# ProPrj_SW4_poor.net
KiCad netlist of a schematic drawn in EasyEDA Pro
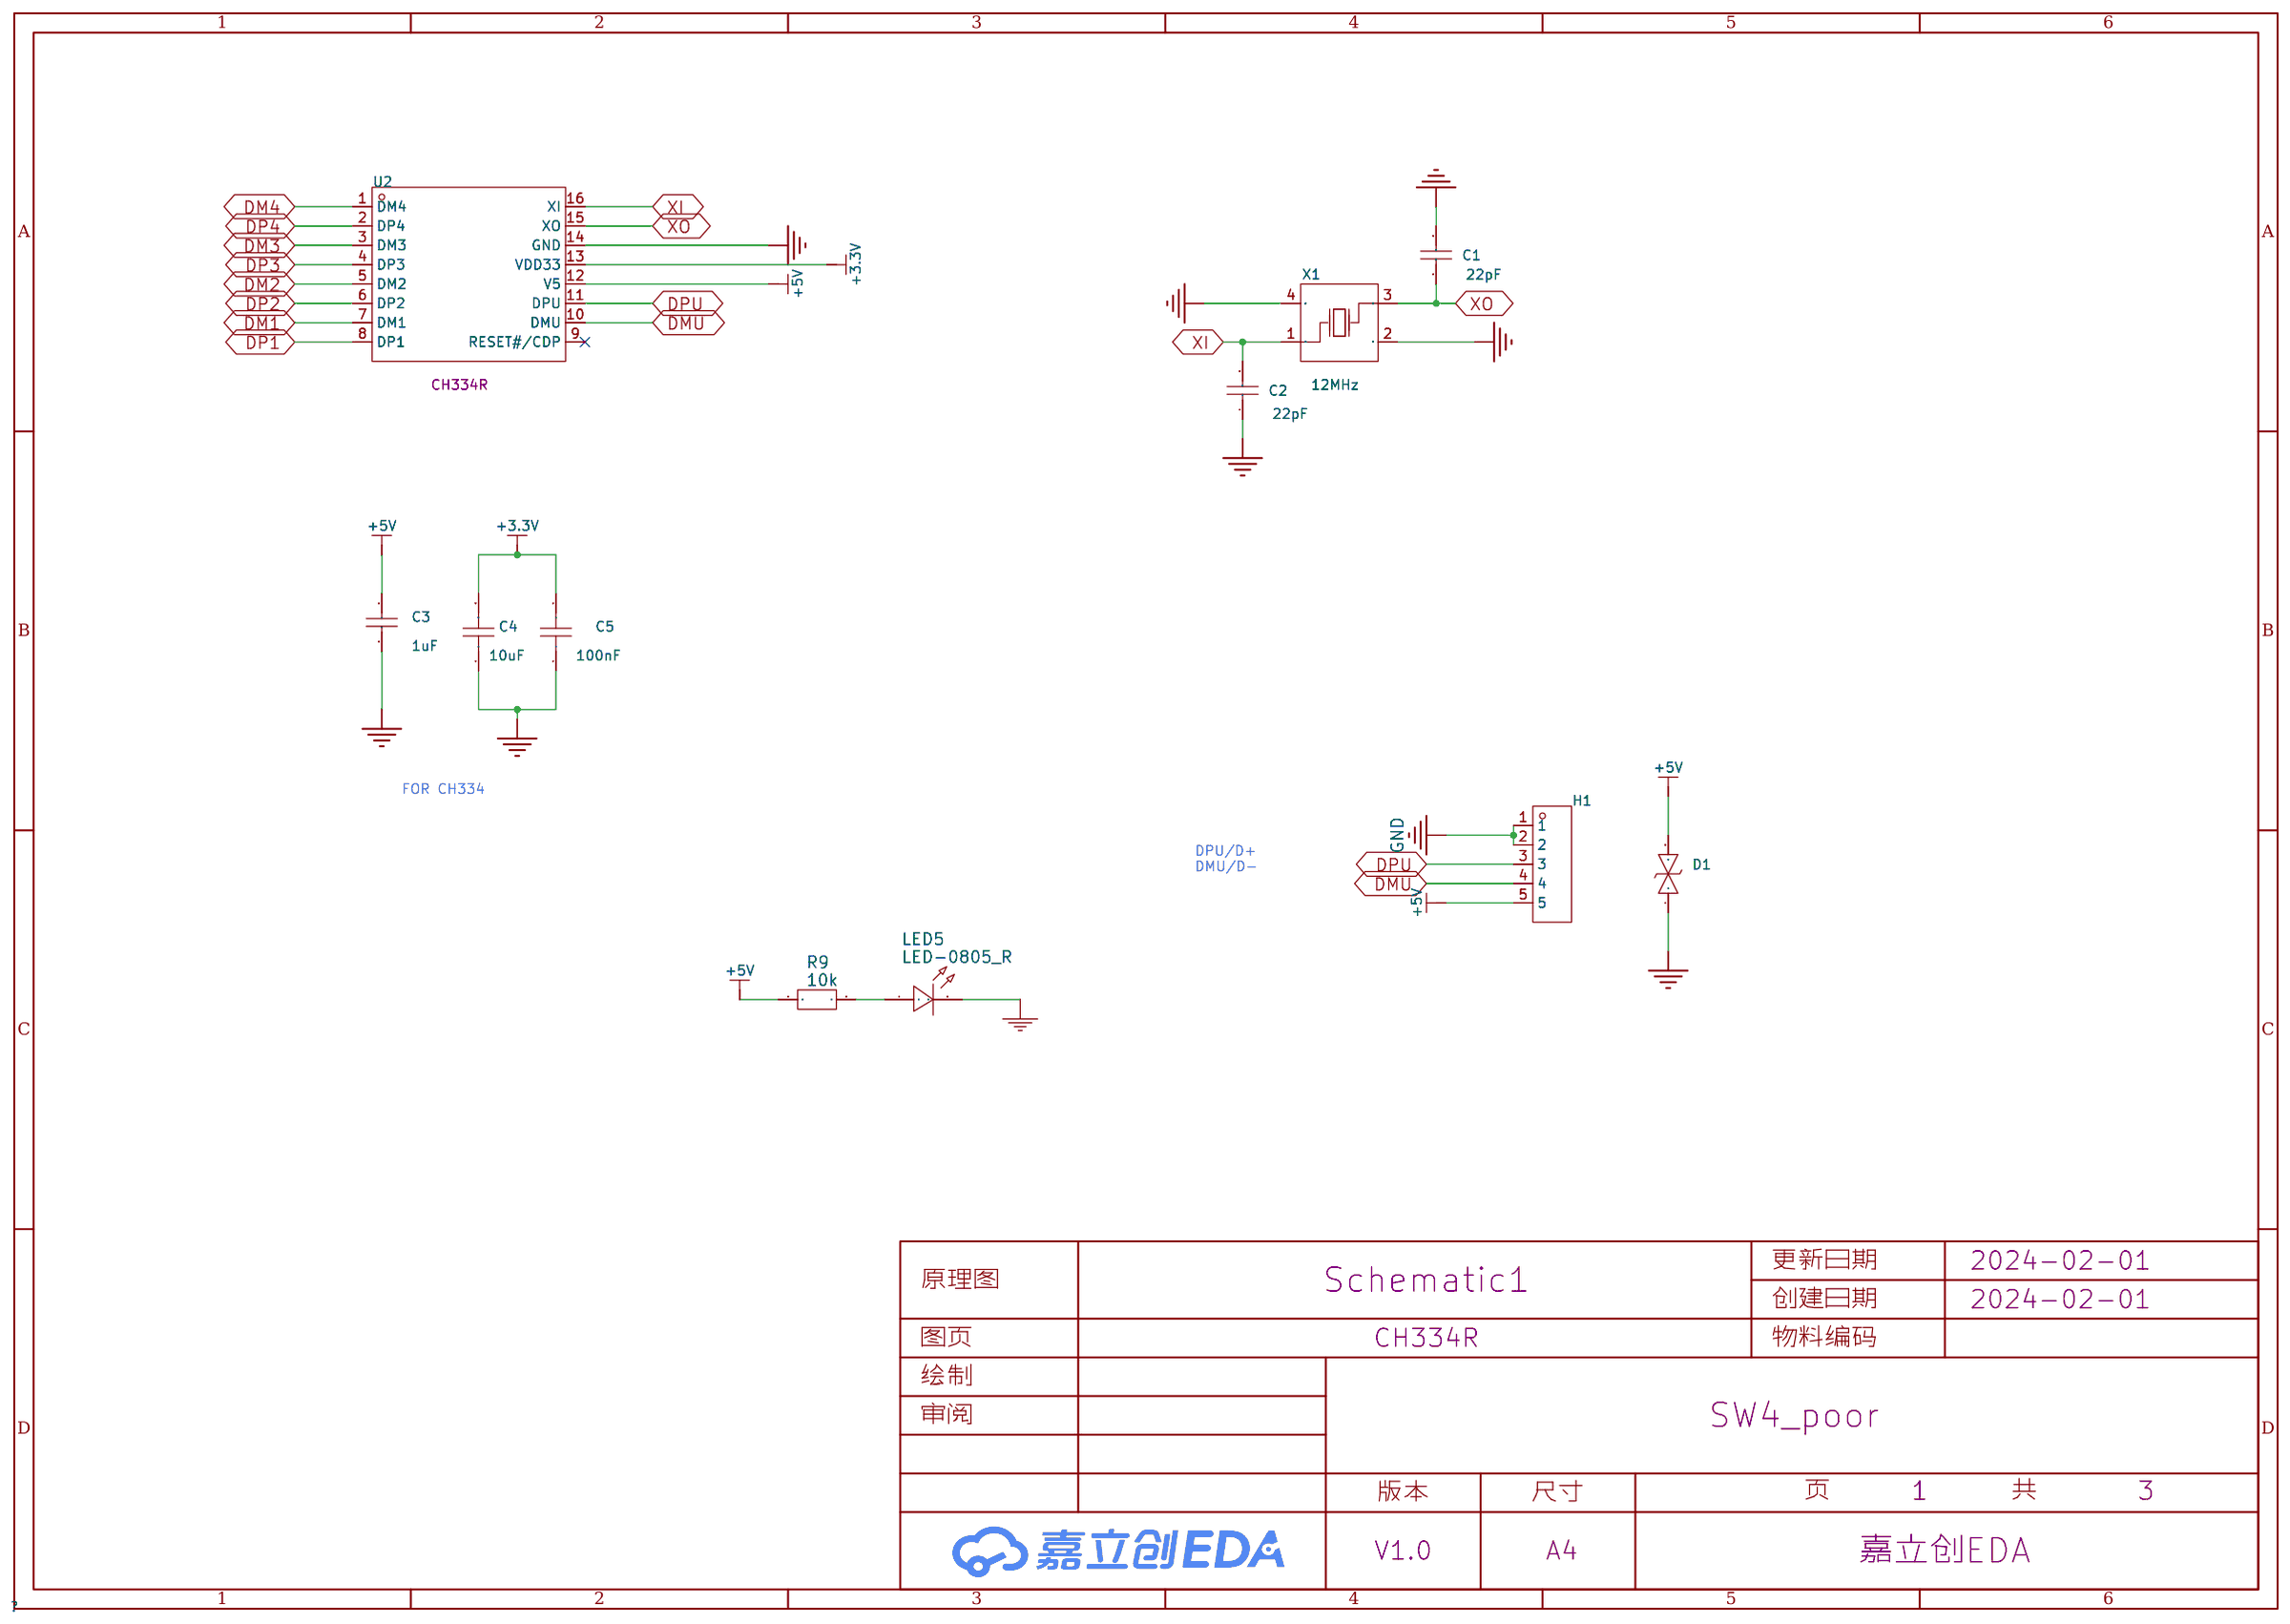
[diagram p0: CH334R]
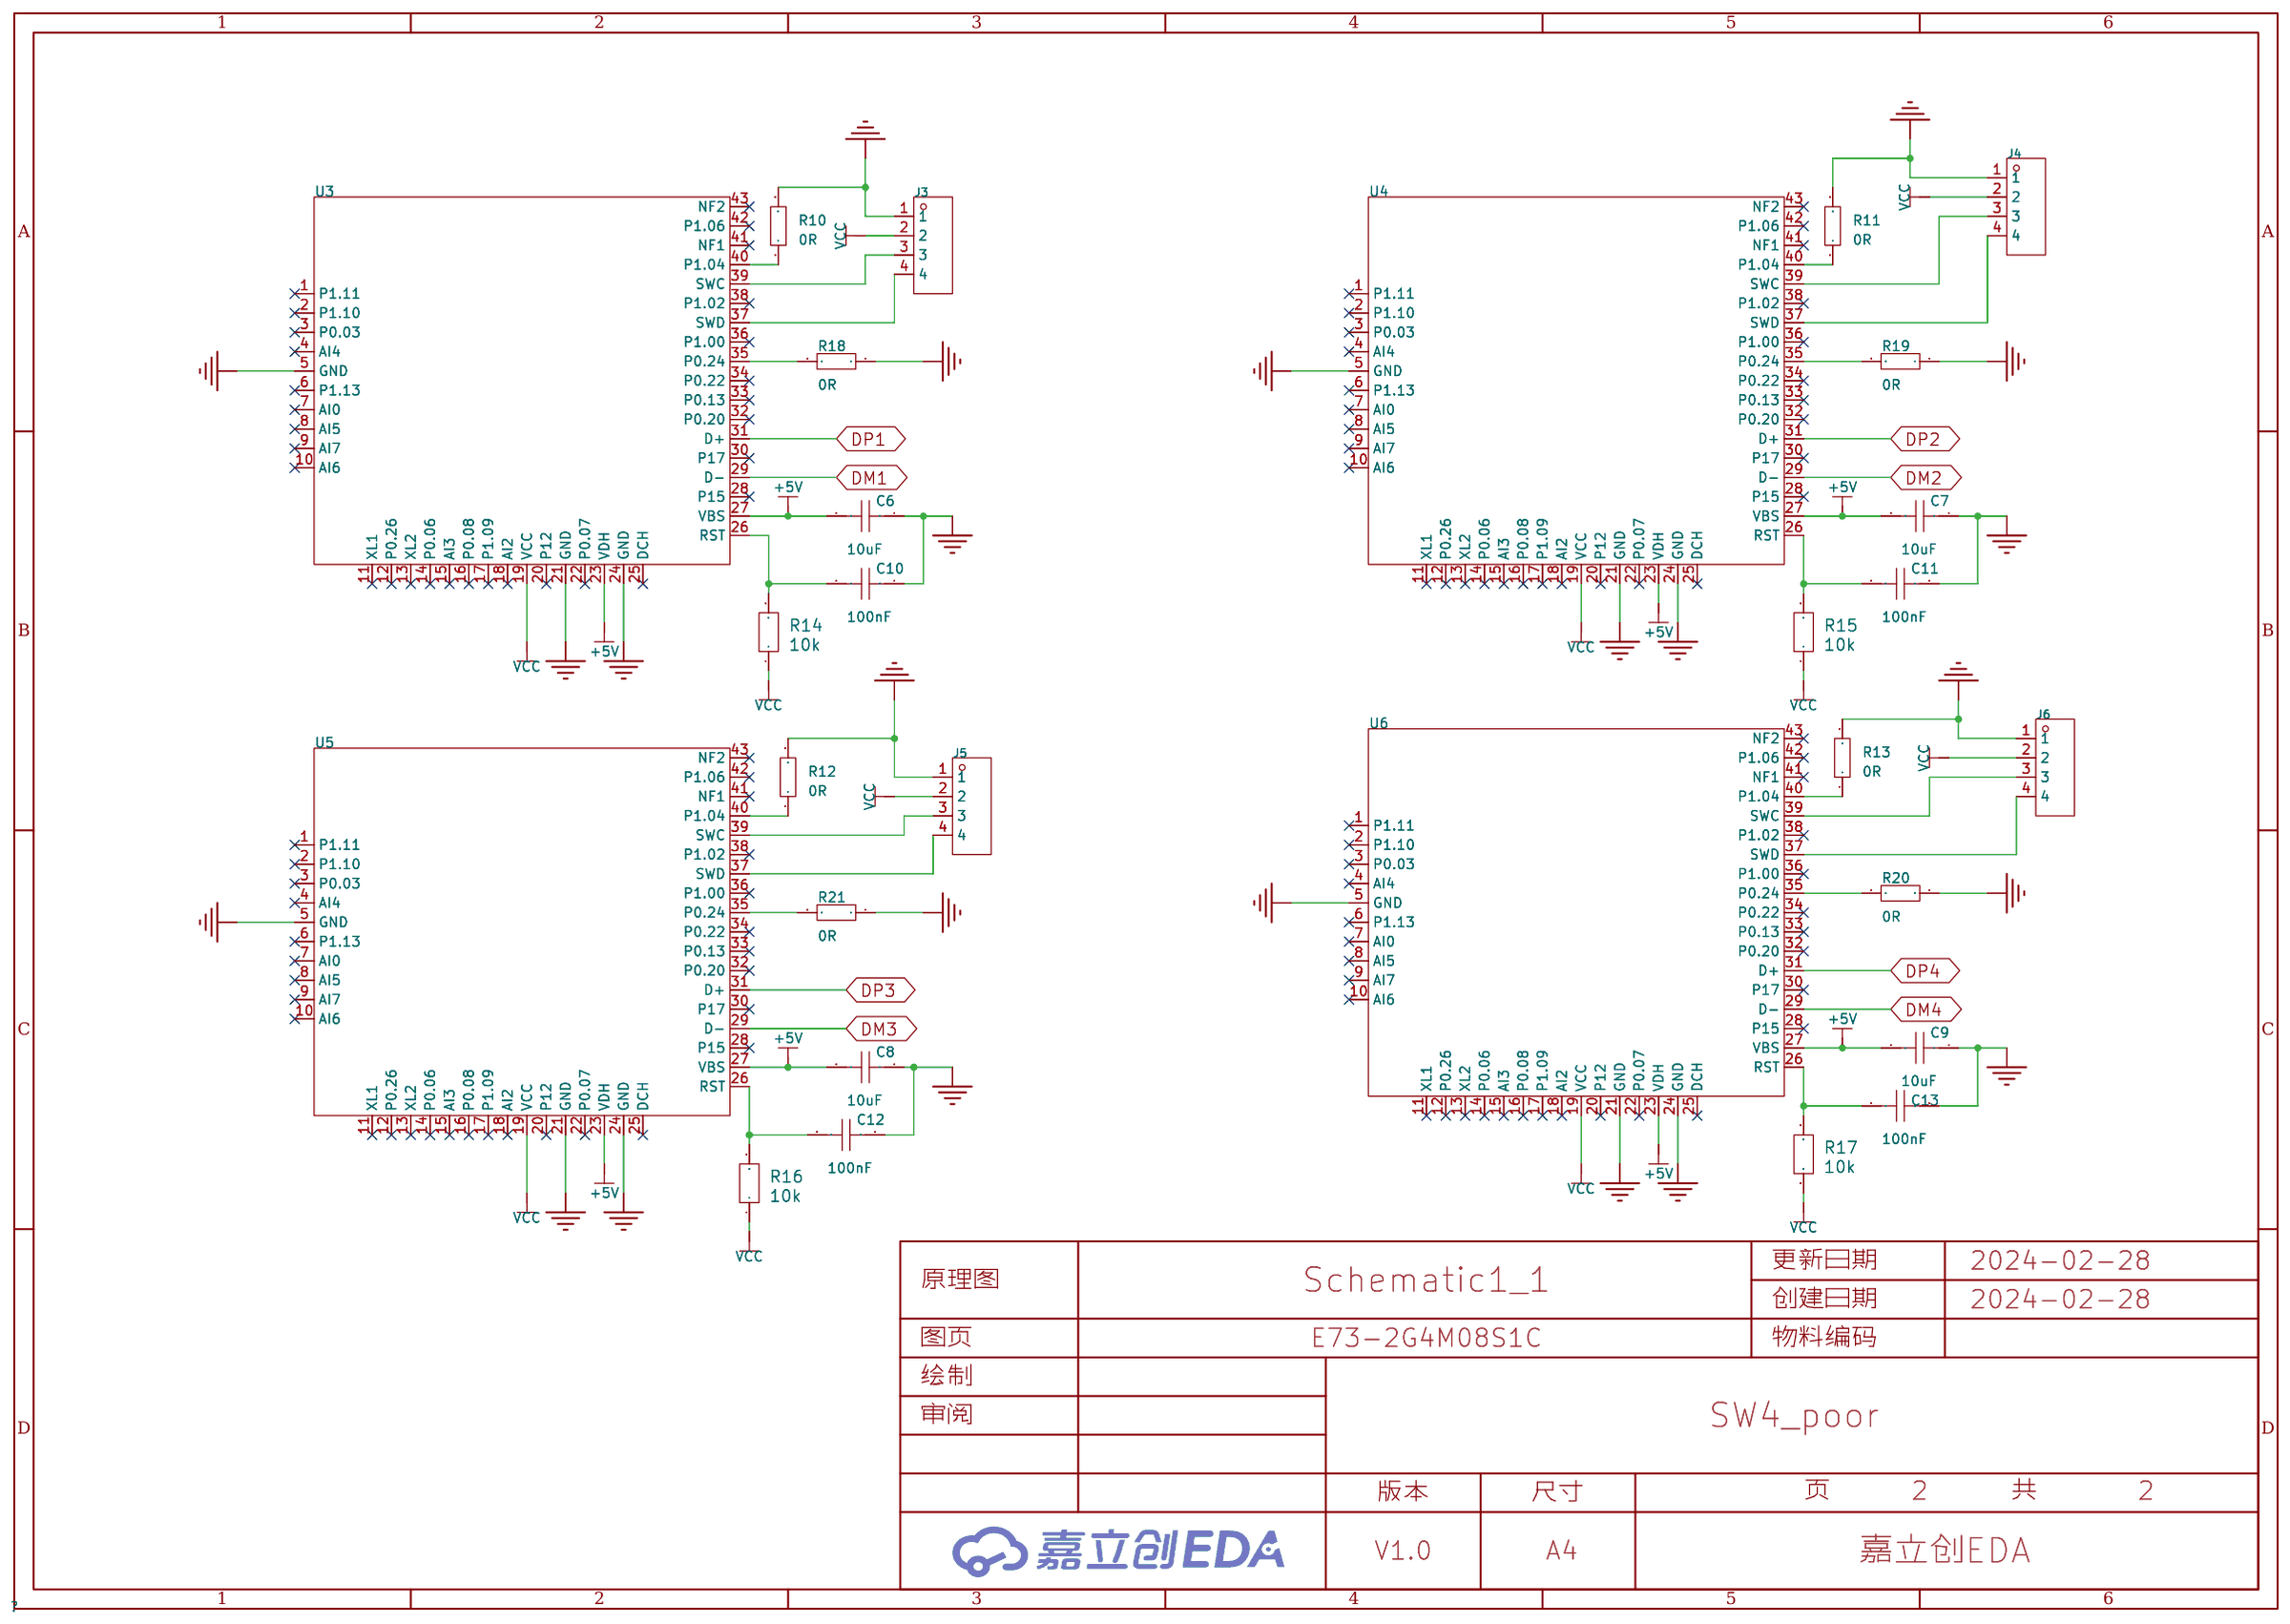
[diagram p1: E73-2G4M08S1C]

(export (version "E")
  (design (tool "Eeschema 10.0.6"))
  (components
    (comp (ref "C1")
      (value "22pF")
      (footprint "easyedapro:C0603")
      (description "容值:22pF;精度:±5%;额定电压:50V;材质(温度系数):C0G;")
      (fields
        (field (name "Manufacturer Part") "CL10C220JB8NNNC")
        (field (name "Manufacturer") "SAMSUNG(三星)")
      )
      (libsource (lib "easyedapro") (part "CL10C220JB8NNNC"))
    )
    (comp (ref "C2")
      (value "22pF")
      (footprint "easyedapro:C0603")
      (description "容值:22pF;精度:±5%;额定电压:50V;材质(温度系数):C0G;")
      (fields
        (field (name "Manufacturer Part") "CL10C220JB8NNNC")
        (field (name "Manufacturer") "SAMSUNG(三星)")
      )
      (libsource (lib "easyedapro") (part "CL10C220JB8NNNC"))
    )
    (comp (ref "C3")
      (value "1uF")
      (footprint "easyedapro:C0603")
      (description "容值:1uF;精度:±10%;额定电压:50V;材质(温度系数):X5R;")
      (fields
        (field (name "Manufacturer Part") "CL10A105KB8NNNC")
        (field (name "Manufacturer") "SAMSUNG(三星)")
      )
      (libsource (lib "easyedapro") (part "CL10A105KB8NNNC"))
    )
    (comp (ref "C4")
      (value "10uF")
      (footprint "easyedapro:C0603")
      (description "容值:10uF;精度:±10%;额定电压:10V;材质(温度系数):X5R;")
      (fields
        (field (name "Manufacturer Part") "CL10A106KP8NNNC")
        (field (name "Manufacturer") "SAMSUNG(三星)")
      )
      (libsource (lib "easyedapro") (part "CL10A106KP8NNNC"))
    )
    (comp (ref "C5")
      (value "100nF")
      (footprint "easyedapro:C0603")
      (description "容值:100nF;精度:±10%;额定电压:50V;材质(温度系数):X7R;")
      (fields
        (field (name "Manufacturer Part") "CC0603KRX7R9BB104")
        (field (name "Manufacturer") "YAGEO(国巨)")
      )
      (libsource (lib "easyedapro") (part "CC0603KRX7R9BB104"))
    )
    (comp (ref "D1")
      (value "SMF5.0CA")
      (footprint "easyedapro:SOD-123_L2.7-W1.8-LS3.7-BI")
      (description "极性:双向;反向截止电压(Vrwm):5V;击穿电压:6.4V;反向漏电流(Ir):800uA;峰值脉冲电流(Ipp)@10/1000μs:21.7A;最大钳位电压:9.2V;")
      (fields (field (name "Manufacturer") "AnBon(安邦)"))
      (libsource (lib "easyedapro") (part "SMF5.0CA_C435453"))
    )
    (comp (ref "H1")
      (value "BX-PH2.0-5PWZ")
      (footprint "easyedapro:CONN-TH_5P-P2.00_BX-PH2.0-5PWZ")
      (fields (field (name "Manufacturer") "Bossie(博锡)"))
      (libsource (lib "easyedapro") (part "BX-PH2.0-5PWZ"))
    )
    (comp (ref "LED5")
      (value "LED-0805_R")
      (footprint "easyedapro:LED0805_RED")
      (fields
        (field (name "Manufacturer Part") "17-21SURC/S530-A3/TR8")
        (field (name "Manufacturer") "EVERLIGHT(台湾亿光)")
      )
      (libsource (lib "easyedapro") (part "LED-0805_R"))
    )
    (comp (ref "R9") (value "10k") (footprint "easyedapro:R0805") (libsource (lib "easyedapro") (part "1k")))
    (comp (ref "U2")
      (value "CH334R")
      (footprint "easyedapro:QSOP-16_L4.9-W3.9-P0.64-LS6.0-BL")
      (fields (field (name "Manufacturer Part") "CH334R") (field (name "Manufacturer") "WCH(南京沁恒)"))
      (libsource (lib "easyedapro") (part "CH334R"))
    )
    (comp (ref "X1")
      (value "12MHz")
      (footprint "easyedapro:OSC-SMD_4P-L3.2-W2.5-BL")
      (description "晶振类型:贴片无源晶振;频率:12MHz;频率公差:±10ppm;频率稳定度:±30ppm;负载电容:12pF;工作温度:-40°C~+85°C;")
      (fields (field (name "Manufacturer Part") "X322512MOB4SI") (field (name "Manufacturer") "YXC(扬兴晶振)"))
      (libsource (lib "easyedapro") (part "X322512MOB4SI"))
    )
    (comp (ref "C6")
      (value "10uF")
      (footprint "easyedapro:C0603")
      (description "容值:10uF;精度:±10%;额定电压:10V;材质(温度系数):X5R;")
      (fields
        (field (name "Manufacturer Part") "CL10A106KP8NNNC")
        (field (name "Manufacturer") "SAMSUNG(三星)")
      )
      (libsource (lib "easyedapro") (part "CL10A106KP8NNNC"))
    )
    (comp (ref "C7")
      (value "10uF")
      (footprint "easyedapro:C0603")
      (description "容值:10uF;精度:±10%;额定电压:10V;材质(温度系数):X5R;")
      (fields
        (field (name "Manufacturer Part") "CL10A106KP8NNNC")
        (field (name "Manufacturer") "SAMSUNG(三星)")
      )
      (libsource (lib "easyedapro") (part "CL10A106KP8NNNC"))
    )
    (comp (ref "C8")
      (value "10uF")
      (footprint "easyedapro:C0603")
      (description "容值:10uF;精度:±10%;额定电压:10V;材质(温度系数):X5R;")
      (fields
        (field (name "Manufacturer Part") "CL10A106KP8NNNC")
        (field (name "Manufacturer") "SAMSUNG(三星)")
      )
      (libsource (lib "easyedapro") (part "CL10A106KP8NNNC"))
    )
    (comp (ref "C9")
      (value "10uF")
      (footprint "easyedapro:C0603")
      (description "容值:10uF;精度:±10%;额定电压:10V;材质(温度系数):X5R;")
      (fields
        (field (name "Manufacturer Part") "CL10A106KP8NNNC")
        (field (name "Manufacturer") "SAMSUNG(三星)")
      )
      (libsource (lib "easyedapro") (part "CL10A106KP8NNNC"))
    )
    (comp (ref "C10")
      (value "100nF")
      (footprint "easyedapro:C0603")
      (description "容值:10uF;精度:±10%;额定电压:10V;材质(温度系数):X5R;")
      (fields
        (field (name "Manufacturer Part") "CL10A106KP8NNNC")
        (field (name "Manufacturer") "SAMSUNG(三星)")
      )
      (libsource (lib "easyedapro") (part "CL10A106KP8NNNC"))
    )
    (comp (ref "C11")
      (value "100nF")
      (footprint "easyedapro:C0603")
      (description "容值:10uF;精度:±10%;额定电压:10V;材质(温度系数):X5R;")
      (fields
        (field (name "Manufacturer Part") "CL10A106KP8NNNC")
        (field (name "Manufacturer") "SAMSUNG(三星)")
      )
      (libsource (lib "easyedapro") (part "CL10A106KP8NNNC"))
    )
    (comp (ref "C12")
      (value "100nF")
      (footprint "easyedapro:C0603")
      (description "容值:10uF;精度:±10%;额定电压:10V;材质(温度系数):X5R;")
      (fields
        (field (name "Manufacturer Part") "CL10A106KP8NNNC")
        (field (name "Manufacturer") "SAMSUNG(三星)")
      )
      (libsource (lib "easyedapro") (part "CL10A106KP8NNNC"))
    )
    (comp (ref "C13")
      (value "100nF")
      (footprint "easyedapro:C0603")
      (description "容值:10uF;精度:±10%;额定电压:10V;材质(温度系数):X5R;")
      (fields
        (field (name "Manufacturer Part") "CL10A106KP8NNNC")
        (field (name "Manufacturer") "SAMSUNG(三星)")
      )
      (libsource (lib "easyedapro") (part "CL10A106KP8NNNC"))
    )
    (comp (ref "J3")
      (value "2.54-4P ZZDK")
      (footprint "easyedapro:HDR-TH_4P-P2.50-V-F-2")
      (fields (field (name "Manufacturer") "SHOU HAN(首韩)"))
      (libsource (lib "easyedapro") (part "2.54-4P ZZDK"))
    )
    (comp (ref "J4")
      (value "2.54-4P ZZDK")
      (footprint "easyedapro:HDR-TH_4P-P2.50-V-F-2")
      (fields (field (name "Manufacturer") "SHOU HAN(首韩)"))
      (libsource (lib "easyedapro") (part "2.54-4P ZZDK"))
    )
    (comp (ref "J5")
      (value "2.54-4P ZZDK")
      (footprint "easyedapro:HDR-TH_4P-P2.50-V-F-2")
      (fields (field (name "Manufacturer") "SHOU HAN(首韩)"))
      (libsource (lib "easyedapro") (part "2.54-4P ZZDK"))
    )
    (comp (ref "J6")
      (value "2.54-4P ZZDK")
      (footprint "easyedapro:HDR-TH_4P-P2.50-V-F-2")
      (fields (field (name "Manufacturer") "SHOU HAN(首韩)"))
      (libsource (lib "easyedapro") (part "2.54-4P ZZDK"))
    )
    (comp (ref "R10") (value "0R") (footprint "easyedapro:R0603") (libsource (lib "easyedapro") (part "电阻")))
    (comp (ref "R11") (value "0R") (footprint "easyedapro:R0603") (libsource (lib "easyedapro") (part "电阻")))
    (comp (ref "R12") (value "0R") (footprint "easyedapro:R0603") (libsource (lib "easyedapro") (part "电阻")))
    (comp (ref "R13") (value "0R") (footprint "easyedapro:R0603") (libsource (lib "easyedapro") (part "电阻")))
    (comp (ref "R14") (value "10k") (footprint "easyedapro:R0805") (libsource (lib "easyedapro") (part "1k")))
    (comp (ref "R15") (value "10k") (footprint "easyedapro:R0805") (libsource (lib "easyedapro") (part "1k")))
    (comp (ref "R16") (value "10k") (footprint "easyedapro:R0805") (libsource (lib "easyedapro") (part "1k")))
    (comp (ref "R17") (value "10k") (footprint "easyedapro:R0805") (libsource (lib "easyedapro") (part "1k")))
    (comp (ref "R18") (value "0R") (footprint "easyedapro:R0603") (libsource (lib "easyedapro") (part "电阻")))
    (comp (ref "R19") (value "0R") (footprint "easyedapro:R0603") (libsource (lib "easyedapro") (part "电阻")))
    (comp (ref "R20") (value "0R") (footprint "easyedapro:R0603") (libsource (lib "easyedapro") (part "电阻")))
    (comp (ref "R21") (value "0R") (footprint "easyedapro:R0603") (libsource (lib "easyedapro") (part "电阻")))
    (comp (ref "U3")
      (value "E73-2G4M08S1C")
      (footprint "easyedapro:WIRELM-SMD_E73-2G4M08S1C")
      (description "nRF52840 BLE Module 低功耗蓝牙")
      (fields (field (name "Manufacturer") "EBYTE(亿佰特)"))
      (libsource (lib "easyedapro") (part "E73-2G4M08S1C"))
    )
    (comp (ref "U4")
      (value "E73-2G4M08S1C")
      (footprint "easyedapro:WIRELM-SMD_E73-2G4M08S1C")
      (description "nRF52840 BLE Module 低功耗蓝牙")
      (fields (field (name "Manufacturer") "EBYTE(亿佰特)"))
      (libsource (lib "easyedapro") (part "E73-2G4M08S1C"))
    )
    (comp (ref "U5")
      (value "E73-2G4M08S1C")
      (footprint "easyedapro:WIRELM-SMD_E73-2G4M08S1C")
      (description "nRF52840 BLE Module 低功耗蓝牙")
      (fields (field (name "Manufacturer") "EBYTE(亿佰特)"))
      (libsource (lib "easyedapro") (part "E73-2G4M08S1C"))
    )
    (comp (ref "U6")
      (value "E73-2G4M08S1C")
      (footprint "easyedapro:WIRELM-SMD_E73-2G4M08S1C")
      (description "nRF52840 BLE Module 低功耗蓝牙")
      (fields (field (name "Manufacturer") "EBYTE(亿佰特)"))
      (libsource (lib "easyedapro") (part "E73-2G4M08S1C"))
    )
  )
  (nets
    (net (code "1") (name "+3.3V") (class "Default")
      (node (ref "C4") (pin "2") (pinfunction "2_2") (pintype "input"))
      (node (ref "C5") (pin "2") (pinfunction "2_2") (pintype "input"))
      (node (ref "U2") (pin "13") (pinfunction "VDD33_13") (pintype "unspecified"))
    )
    (net (code "2") (name "+5V") (class "Default")
      (node (ref "C3") (pin "2") (pinfunction "2_2") (pintype "input"))
      (node (ref "C6") (pin "2") (pinfunction "2_2") (pintype "input"))
      (node (ref "C7") (pin "2") (pinfunction "2_2") (pintype "input"))
      (node (ref "C8") (pin "2") (pinfunction "2_2") (pintype "input"))
      (node (ref "C9") (pin "2") (pinfunction "2_2") (pintype "input"))
      (node (ref "D1") (pin "2") (pinfunction "2_2") (pintype "input"))
      (node (ref "H1") (pin "5") (pinfunction "5_5") (pintype "unspecified"))
      (node (ref "R9") (pin "1") (pinfunction "1_1") (pintype "input"))
      (node (ref "U2") (pin "12") (pinfunction "V5_12") (pintype "unspecified"))
      (node (ref "U3") (pin "23") (pinfunction "VDH_23") (pintype "input"))
      (node (ref "U3") (pin "27") (pinfunction "VBS_27") (pintype "input"))
      (node (ref "U4") (pin "23") (pinfunction "VDH_23") (pintype "input"))
      (node (ref "U4") (pin "27") (pinfunction "VBS_27") (pintype "input"))
      (node (ref "U5") (pin "23") (pinfunction "VDH_23") (pintype "input"))
      (node (ref "U5") (pin "27") (pinfunction "VBS_27") (pintype "input"))
      (node (ref "U6") (pin "23") (pinfunction "VDH_23") (pintype "input"))
      (node (ref "U6") (pin "27") (pinfunction "VBS_27") (pintype "input"))
    )
    (net (code "3") (name "DM1") (class "Default")
      (node (ref "U2") (pin "7") (pinfunction "DM1_7") (pintype "unspecified"))
      (node (ref "U3") (pin "29") (pinfunction "D-_29") (pintype "input"))
    )
    (net (code "4") (name "DM2") (class "Default")
      (node (ref "U2") (pin "5") (pinfunction "DM2_5") (pintype "unspecified"))
      (node (ref "U4") (pin "29") (pinfunction "D-_29") (pintype "input"))
    )
    (net (code "5") (name "DM3") (class "Default")
      (node (ref "U2") (pin "3") (pinfunction "DM3_3") (pintype "unspecified"))
      (node (ref "U5") (pin "29") (pinfunction "D-_29") (pintype "input"))
    )
    (net (code "6") (name "DM4") (class "Default")
      (node (ref "U2") (pin "1") (pinfunction "DM4_1") (pintype "unspecified"))
      (node (ref "U6") (pin "29") (pinfunction "D-_29") (pintype "input"))
    )
    (net (code "7") (name "DMU") (class "Default")
      (node (ref "H1") (pin "4") (pinfunction "4_4") (pintype "unspecified"))
      (node (ref "U2") (pin "10") (pinfunction "DMU_10") (pintype "unspecified"))
    )
    (net (code "8") (name "DP1") (class "Default")
      (node (ref "U2") (pin "8") (pinfunction "DP1_8") (pintype "unspecified"))
      (node (ref "U3") (pin "31") (pinfunction "D+_31") (pintype "input"))
    )
    (net (code "9") (name "DP2") (class "Default")
      (node (ref "U2") (pin "6") (pinfunction "DP2_6") (pintype "unspecified"))
      (node (ref "U4") (pin "31") (pinfunction "D+_31") (pintype "input"))
    )
    (net (code "10") (name "DP3") (class "Default")
      (node (ref "U2") (pin "4") (pinfunction "DP3_4") (pintype "unspecified"))
      (node (ref "U5") (pin "31") (pinfunction "D+_31") (pintype "input"))
    )
    (net (code "11") (name "DP4") (class "Default")
      (node (ref "U2") (pin "2") (pinfunction "DP4_2") (pintype "unspecified"))
      (node (ref "U6") (pin "31") (pinfunction "D+_31") (pintype "input"))
    )
    (net (code "12") (name "DPU") (class "Default")
      (node (ref "H1") (pin "3") (pinfunction "3_3") (pintype "unspecified"))
      (node (ref "U2") (pin "11") (pinfunction "DPU_11") (pintype "unspecified"))
    )
    (net (code "13") (name "GND") (class "Default")
      (node (ref "C1") (pin "2") (pinfunction "2_2") (pintype "input"))
      (node (ref "C10") (pin "1") (pinfunction "1_1") (pintype "input"))
      (node (ref "C11") (pin "1") (pinfunction "1_1") (pintype "input"))
      (node (ref "C12") (pin "1") (pinfunction "1_1") (pintype "input"))
      (node (ref "C13") (pin "1") (pinfunction "1_1") (pintype "input"))
      (node (ref "C2") (pin "1") (pinfunction "1_1") (pintype "input"))
      (node (ref "C3") (pin "1") (pinfunction "1_1") (pintype "input"))
      (node (ref "C4") (pin "1") (pinfunction "1_1") (pintype "input"))
      (node (ref "C5") (pin "1") (pinfunction "1_1") (pintype "input"))
      (node (ref "C6") (pin "1") (pinfunction "1_1") (pintype "input"))
      (node (ref "C7") (pin "1") (pinfunction "1_1") (pintype "input"))
      (node (ref "C8") (pin "1") (pinfunction "1_1") (pintype "input"))
      (node (ref "C9") (pin "1") (pinfunction "1_1") (pintype "input"))
      (node (ref "D1") (pin "1") (pinfunction "1_1") (pintype "input"))
      (node (ref "H1") (pin "1") (pinfunction "1_1") (pintype "unspecified"))
      (node (ref "H1") (pin "2") (pinfunction "2_2") (pintype "unspecified"))
      (node (ref "J3") (pin "1") (pinfunction "1_1") (pintype "input"))
      (node (ref "J4") (pin "1") (pinfunction "1_1") (pintype "input"))
      (node (ref "J5") (pin "1") (pinfunction "1_1") (pintype "input"))
      (node (ref "J6") (pin "1") (pinfunction "1_1") (pintype "input"))
      (node (ref "LED5") (pin "2") (pinfunction "2_2") (pintype "input"))
      (node (ref "R10") (pin "2") (pinfunction "2_2") (pintype "input"))
      (node (ref "R11") (pin "2") (pinfunction "2_2") (pintype "input"))
      (node (ref "R12") (pin "2") (pinfunction "2_2") (pintype "input"))
      (node (ref "R13") (pin "2") (pinfunction "2_2") (pintype "input"))
      (node (ref "R18") (pin "1") (pinfunction "1_1") (pintype "input"))
      (node (ref "R19") (pin "1") (pinfunction "1_1") (pintype "input"))
      (node (ref "R20") (pin "1") (pinfunction "1_1") (pintype "input"))
      (node (ref "R21") (pin "1") (pinfunction "1_1") (pintype "input"))
      (node (ref "U2") (pin "14") (pinfunction "GND_14") (pintype "unspecified"))
      (node (ref "U3") (pin "21") (pinfunction "GND_21") (pintype "input"))
      (node (ref "U3") (pin "24") (pinfunction "GND_24") (pintype "input"))
      (node (ref "U3") (pin "5") (pinfunction "GND_5") (pintype "input"))
      (node (ref "U4") (pin "21") (pinfunction "GND_21") (pintype "input"))
      (node (ref "U4") (pin "24") (pinfunction "GND_24") (pintype "input"))
      (node (ref "U4") (pin "5") (pinfunction "GND_5") (pintype "input"))
      (node (ref "U5") (pin "21") (pinfunction "GND_21") (pintype "input"))
      (node (ref "U5") (pin "24") (pinfunction "GND_24") (pintype "input"))
      (node (ref "U5") (pin "5") (pinfunction "GND_5") (pintype "input"))
      (node (ref "U6") (pin "21") (pinfunction "GND_21") (pintype "input"))
      (node (ref "U6") (pin "24") (pinfunction "GND_24") (pintype "input"))
      (node (ref "U6") (pin "5") (pinfunction "GND_5") (pintype "input"))
      (node (ref "X1") (pin "2") (pinfunction "GND_2") (pintype "input"))
      (node (ref "X1") (pin "4") (pinfunction "GND_4") (pintype "input"))
    )
    (net (code "14") (name "Net-(LED5-Pad1)") (class "Default")
      (node (ref "LED5") (pin "1") (pinfunction "1_1") (pintype "input"))
      (node (ref "R9") (pin "2") (pinfunction "2_2") (pintype "input"))
    )
    (net (code "15") (name "Net-(U3-P0.24)") (class "Default")
      (node (ref "R18") (pin "2") (pinfunction "2_2") (pintype "input"))
      (node (ref "U3") (pin "35") (pinfunction "P0.24_35") (pintype "input"))
    )
    (net (code "16") (name "Net-(U3-P1.04)") (class "Default")
      (node (ref "R10") (pin "1") (pinfunction "1_1") (pintype "input"))
      (node (ref "U3") (pin "40") (pinfunction "P1.04_40") (pintype "input"))
    )
    (net (code "17") (name "Net-(U3-RST)") (class "Default")
      (node (ref "C10") (pin "2") (pinfunction "2_2") (pintype "input"))
      (node (ref "R14") (pin "2") (pinfunction "2_2") (pintype "input"))
      (node (ref "U3") (pin "26") (pinfunction "RST_26") (pintype "input"))
    )
    (net (code "18") (name "Net-(U3-SWC)") (class "Default")
      (node (ref "J3") (pin "3") (pinfunction "3_3") (pintype "input"))
      (node (ref "U3") (pin "39") (pinfunction "SWC_39") (pintype "input"))
    )
    (net (code "19") (name "Net-(U3-SWD)") (class "Default")
      (node (ref "J3") (pin "4") (pinfunction "4_4") (pintype "input"))
      (node (ref "U3") (pin "37") (pinfunction "SWD_37") (pintype "input"))
    )
    (net (code "20") (name "Net-(U4-P0.24)") (class "Default")
      (node (ref "R19") (pin "2") (pinfunction "2_2") (pintype "input"))
      (node (ref "U4") (pin "35") (pinfunction "P0.24_35") (pintype "input"))
    )
    (net (code "21") (name "Net-(U4-P1.04)") (class "Default")
      (node (ref "R11") (pin "1") (pinfunction "1_1") (pintype "input"))
      (node (ref "U4") (pin "40") (pinfunction "P1.04_40") (pintype "input"))
    )
    (net (code "22") (name "Net-(U4-RST)") (class "Default")
      (node (ref "C11") (pin "2") (pinfunction "2_2") (pintype "input"))
      (node (ref "R15") (pin "2") (pinfunction "2_2") (pintype "input"))
      (node (ref "U4") (pin "26") (pinfunction "RST_26") (pintype "input"))
    )
    (net (code "23") (name "Net-(U4-SWC)") (class "Default")
      (node (ref "J4") (pin "3") (pinfunction "3_3") (pintype "input"))
      (node (ref "U4") (pin "39") (pinfunction "SWC_39") (pintype "input"))
    )
    (net (code "24") (name "Net-(U4-SWD)") (class "Default")
      (node (ref "J4") (pin "4") (pinfunction "4_4") (pintype "input"))
      (node (ref "U4") (pin "37") (pinfunction "SWD_37") (pintype "input"))
    )
    (net (code "25") (name "Net-(U5-P0.24)") (class "Default")
      (node (ref "R21") (pin "2") (pinfunction "2_2") (pintype "input"))
      (node (ref "U5") (pin "35") (pinfunction "P0.24_35") (pintype "input"))
    )
    (net (code "26") (name "Net-(U5-P1.04)") (class "Default")
      (node (ref "R12") (pin "1") (pinfunction "1_1") (pintype "input"))
      (node (ref "U5") (pin "40") (pinfunction "P1.04_40") (pintype "input"))
    )
    (net (code "27") (name "Net-(U5-RST)") (class "Default")
      (node (ref "C12") (pin "2") (pinfunction "2_2") (pintype "input"))
      (node (ref "R16") (pin "2") (pinfunction "2_2") (pintype "input"))
      (node (ref "U5") (pin "26") (pinfunction "RST_26") (pintype "input"))
    )
    (net (code "28") (name "Net-(U5-SWC)") (class "Default")
      (node (ref "J5") (pin "3") (pinfunction "3_3") (pintype "input"))
      (node (ref "U5") (pin "39") (pinfunction "SWC_39") (pintype "input"))
    )
    (net (code "29") (name "Net-(U5-SWD)") (class "Default")
      (node (ref "J5") (pin "4") (pinfunction "4_4") (pintype "input"))
      (node (ref "U5") (pin "37") (pinfunction "SWD_37") (pintype "input"))
    )
    (net (code "30") (name "Net-(U6-P0.24)") (class "Default")
      (node (ref "R20") (pin "2") (pinfunction "2_2") (pintype "input"))
      (node (ref "U6") (pin "35") (pinfunction "P0.24_35") (pintype "input"))
    )
    (net (code "31") (name "Net-(U6-P1.04)") (class "Default")
      (node (ref "R13") (pin "1") (pinfunction "1_1") (pintype "input"))
      (node (ref "U6") (pin "40") (pinfunction "P1.04_40") (pintype "input"))
    )
    (net (code "32") (name "Net-(U6-RST)") (class "Default")
      (node (ref "C13") (pin "2") (pinfunction "2_2") (pintype "input"))
      (node (ref "R17") (pin "2") (pinfunction "2_2") (pintype "input"))
      (node (ref "U6") (pin "26") (pinfunction "RST_26") (pintype "input"))
    )
    (net (code "33") (name "Net-(U6-SWC)") (class "Default")
      (node (ref "J6") (pin "3") (pinfunction "3_3") (pintype "input"))
      (node (ref "U6") (pin "39") (pinfunction "SWC_39") (pintype "input"))
    )
    (net (code "34") (name "Net-(U6-SWD)") (class "Default")
      (node (ref "J6") (pin "4") (pinfunction "4_4") (pintype "input"))
      (node (ref "U6") (pin "37") (pinfunction "SWD_37") (pintype "input"))
    )
    (net (code "35") (name "VCC") (class "Default")
      (node (ref "J3") (pin "2") (pinfunction "2_2") (pintype "input"))
      (node (ref "J4") (pin "2") (pinfunction "2_2") (pintype "input"))
      (node (ref "J5") (pin "2") (pinfunction "2_2") (pintype "input"))
      (node (ref "J6") (pin "2") (pinfunction "2_2") (pintype "input"))
      (node (ref "R14") (pin "1") (pinfunction "1_1") (pintype "input"))
      (node (ref "R15") (pin "1") (pinfunction "1_1") (pintype "input"))
      (node (ref "R16") (pin "1") (pinfunction "1_1") (pintype "input"))
      (node (ref "R17") (pin "1") (pinfunction "1_1") (pintype "input"))
      (node (ref "U3") (pin "19") (pinfunction "VCC_19") (pintype "input"))
      (node (ref "U4") (pin "19") (pinfunction "VCC_19") (pintype "input"))
      (node (ref "U5") (pin "19") (pinfunction "VCC_19") (pintype "input"))
      (node (ref "U6") (pin "19") (pinfunction "VCC_19") (pintype "input"))
    )
    (net (code "36") (name "XI") (class "Default")
      (node (ref "C2") (pin "2") (pinfunction "2_2") (pintype "input"))
      (node (ref "U2") (pin "16") (pinfunction "XI_16") (pintype "unspecified"))
      (node (ref "X1") (pin "1") (pinfunction "OSC1_1") (pintype "input"))
    )
    (net (code "37") (name "XO") (class "Default")
      (node (ref "C1") (pin "1") (pinfunction "1_1") (pintype "input"))
      (node (ref "U2") (pin "15") (pinfunction "XO_15") (pintype "unspecified"))
      (node (ref "X1") (pin "3") (pinfunction "OSC2_3") (pintype "input"))
    )
    (net (code "38") (name "unconnected-(U2-RESET#{slash}CDP-Pad9)") (class "Default")
      (node (ref "U2") (pin "9") (pinfunction "RESET#/CDP_9") (pintype "unspecified+no_connect"))
    )
    (net (code "39") (name "unconnected-(U3-AI0-Pad7)") (class "Default")
      (node (ref "U3") (pin "7") (pinfunction "AI0_7") (pintype "input+no_connect"))
    )
    (net (code "40") (name "unconnected-(U3-AI2-Pad18)") (class "Default")
      (node (ref "U3") (pin "18") (pinfunction "AI2_18") (pintype "input+no_connect"))
    )
    (net (code "41") (name "unconnected-(U3-AI3-Pad15)") (class "Default")
      (node (ref "U3") (pin "15") (pinfunction "AI3_15") (pintype "input+no_connect"))
    )
    (net (code "42") (name "unconnected-(U3-AI4-Pad4)") (class "Default")
      (node (ref "U3") (pin "4") (pinfunction "AI4_4") (pintype "input+no_connect"))
    )
    (net (code "43") (name "unconnected-(U3-AI5-Pad8)") (class "Default")
      (node (ref "U3") (pin "8") (pinfunction "AI5_8") (pintype "input+no_connect"))
    )
    (net (code "44") (name "unconnected-(U3-AI6-Pad10)") (class "Default")
      (node (ref "U3") (pin "10") (pinfunction "AI6_10") (pintype "input+no_connect"))
    )
    (net (code "45") (name "unconnected-(U3-AI7-Pad9)") (class "Default")
      (node (ref "U3") (pin "9") (pinfunction "AI7_9") (pintype "input+no_connect"))
    )
    (net (code "46") (name "unconnected-(U3-DCH-Pad25)") (class "Default")
      (node (ref "U3") (pin "25") (pinfunction "DCH_25") (pintype "input+no_connect"))
    )
    (net (code "47") (name "unconnected-(U3-NF1-Pad41)") (class "Default")
      (node (ref "U3") (pin "41") (pinfunction "NF1_41") (pintype "input+no_connect"))
    )
    (net (code "48") (name "unconnected-(U3-NF2-Pad43)") (class "Default")
      (node (ref "U3") (pin "43") (pinfunction "NF2_43") (pintype "input+no_connect"))
    )
    (net (code "49") (name "unconnected-(U3-P0.03-Pad3)") (class "Default")
      (node (ref "U3") (pin "3") (pinfunction "P0.03_3") (pintype "input+no_connect"))
    )
    (net (code "50") (name "unconnected-(U3-P0.06-Pad14)") (class "Default")
      (node (ref "U3") (pin "14") (pinfunction "P0.06_14") (pintype "input+no_connect"))
    )
    (net (code "51") (name "unconnected-(U3-P0.07-Pad22)") (class "Default")
      (node (ref "U3") (pin "22") (pinfunction "P0.07_22") (pintype "input+no_connect"))
    )
    (net (code "52") (name "unconnected-(U3-P0.08-Pad16)") (class "Default")
      (node (ref "U3") (pin "16") (pinfunction "P0.08_16") (pintype "input+no_connect"))
    )
    (net (code "53") (name "unconnected-(U3-P0.13-Pad33)") (class "Default")
      (node (ref "U3") (pin "33") (pinfunction "P0.13_33") (pintype "input+no_connect"))
    )
    (net (code "54") (name "unconnected-(U3-P0.20-Pad32)") (class "Default")
      (node (ref "U3") (pin "32") (pinfunction "P0.20_32") (pintype "input+no_connect"))
    )
    (net (code "55") (name "unconnected-(U3-P0.22-Pad34)") (class "Default")
      (node (ref "U3") (pin "34") (pinfunction "P0.22_34") (pintype "input+no_connect"))
    )
    (net (code "56") (name "unconnected-(U3-P0.26-Pad12)") (class "Default")
      (node (ref "U3") (pin "12") (pinfunction "P0.26_12") (pintype "input+no_connect"))
    )
    (net (code "57") (name "unconnected-(U3-P1.00-Pad36)") (class "Default")
      (node (ref "U3") (pin "36") (pinfunction "P1.00_36") (pintype "input+no_connect"))
    )
    (net (code "58") (name "unconnected-(U3-P1.02-Pad38)") (class "Default")
      (node (ref "U3") (pin "38") (pinfunction "P1.02_38") (pintype "input+no_connect"))
    )
    (net (code "59") (name "unconnected-(U3-P1.06-Pad42)") (class "Default")
      (node (ref "U3") (pin "42") (pinfunction "P1.06_42") (pintype "input+no_connect"))
    )
    (net (code "60") (name "unconnected-(U3-P1.09-Pad17)") (class "Default")
      (node (ref "U3") (pin "17") (pinfunction "P1.09_17") (pintype "input+no_connect"))
    )
    (net (code "61") (name "unconnected-(U3-P1.10-Pad2)") (class "Default")
      (node (ref "U3") (pin "2") (pinfunction "P1.10_2") (pintype "input+no_connect"))
    )
    (net (code "62") (name "unconnected-(U3-P1.11-Pad1)") (class "Default")
      (node (ref "U3") (pin "1") (pinfunction "P1.11_1") (pintype "input+no_connect"))
    )
    (net (code "63") (name "unconnected-(U3-P1.13-Pad6)") (class "Default")
      (node (ref "U3") (pin "6") (pinfunction "P1.13_6") (pintype "input+no_connect"))
    )
    (net (code "64") (name "unconnected-(U3-P12-Pad20)") (class "Default")
      (node (ref "U3") (pin "20") (pinfunction "P12_20") (pintype "input+no_connect"))
    )
    (net (code "65") (name "unconnected-(U3-P15-Pad28)") (class "Default")
      (node (ref "U3") (pin "28") (pinfunction "P15_28") (pintype "input+no_connect"))
    )
    (net (code "66") (name "unconnected-(U3-P17-Pad30)") (class "Default")
      (node (ref "U3") (pin "30") (pinfunction "P17_30") (pintype "input+no_connect"))
    )
    (net (code "67") (name "unconnected-(U3-XL1-Pad11)") (class "Default")
      (node (ref "U3") (pin "11") (pinfunction "XL1_11") (pintype "input+no_connect"))
    )
    (net (code "68") (name "unconnected-(U3-XL2-Pad13)") (class "Default")
      (node (ref "U3") (pin "13") (pinfunction "XL2_13") (pintype "input+no_connect"))
    )
    (net (code "69") (name "unconnected-(U4-AI0-Pad7)") (class "Default")
      (node (ref "U4") (pin "7") (pinfunction "AI0_7") (pintype "input+no_connect"))
    )
    (net (code "70") (name "unconnected-(U4-AI2-Pad18)") (class "Default")
      (node (ref "U4") (pin "18") (pinfunction "AI2_18") (pintype "input+no_connect"))
    )
    (net (code "71") (name "unconnected-(U4-AI3-Pad15)") (class "Default")
      (node (ref "U4") (pin "15") (pinfunction "AI3_15") (pintype "input+no_connect"))
    )
    (net (code "72") (name "unconnected-(U4-AI4-Pad4)") (class "Default")
      (node (ref "U4") (pin "4") (pinfunction "AI4_4") (pintype "input+no_connect"))
    )
    (net (code "73") (name "unconnected-(U4-AI5-Pad8)") (class "Default")
      (node (ref "U4") (pin "8") (pinfunction "AI5_8") (pintype "input+no_connect"))
    )
    (net (code "74") (name "unconnected-(U4-AI6-Pad10)") (class "Default")
      (node (ref "U4") (pin "10") (pinfunction "AI6_10") (pintype "input+no_connect"))
    )
    (net (code "75") (name "unconnected-(U4-AI7-Pad9)") (class "Default")
      (node (ref "U4") (pin "9") (pinfunction "AI7_9") (pintype "input+no_connect"))
    )
    (net (code "76") (name "unconnected-(U4-DCH-Pad25)") (class "Default")
      (node (ref "U4") (pin "25") (pinfunction "DCH_25") (pintype "input+no_connect"))
    )
    (net (code "77") (name "unconnected-(U4-NF1-Pad41)") (class "Default")
      (node (ref "U4") (pin "41") (pinfunction "NF1_41") (pintype "input+no_connect"))
    )
    (net (code "78") (name "unconnected-(U4-NF2-Pad43)") (class "Default")
      (node (ref "U4") (pin "43") (pinfunction "NF2_43") (pintype "input+no_connect"))
    )
    (net (code "79") (name "unconnected-(U4-P0.03-Pad3)") (class "Default")
      (node (ref "U4") (pin "3") (pinfunction "P0.03_3") (pintype "input+no_connect"))
    )
    (net (code "80") (name "unconnected-(U4-P0.06-Pad14)") (class "Default")
      (node (ref "U4") (pin "14") (pinfunction "P0.06_14") (pintype "input+no_connect"))
    )
    (net (code "81") (name "unconnected-(U4-P0.07-Pad22)") (class "Default")
      (node (ref "U4") (pin "22") (pinfunction "P0.07_22") (pintype "input+no_connect"))
    )
    (net (code "82") (name "unconnected-(U4-P0.08-Pad16)") (class "Default")
      (node (ref "U4") (pin "16") (pinfunction "P0.08_16") (pintype "input+no_connect"))
    )
    (net (code "83") (name "unconnected-(U4-P0.13-Pad33)") (class "Default")
      (node (ref "U4") (pin "33") (pinfunction "P0.13_33") (pintype "input+no_connect"))
    )
    (net (code "84") (name "unconnected-(U4-P0.20-Pad32)") (class "Default")
      (node (ref "U4") (pin "32") (pinfunction "P0.20_32") (pintype "input+no_connect"))
    )
    (net (code "85") (name "unconnected-(U4-P0.22-Pad34)") (class "Default")
      (node (ref "U4") (pin "34") (pinfunction "P0.22_34") (pintype "input+no_connect"))
    )
    (net (code "86") (name "unconnected-(U4-P0.26-Pad12)") (class "Default")
      (node (ref "U4") (pin "12") (pinfunction "P0.26_12") (pintype "input+no_connect"))
    )
    (net (code "87") (name "unconnected-(U4-P1.00-Pad36)") (class "Default")
      (node (ref "U4") (pin "36") (pinfunction "P1.00_36") (pintype "input+no_connect"))
    )
    (net (code "88") (name "unconnected-(U4-P1.02-Pad38)") (class "Default")
      (node (ref "U4") (pin "38") (pinfunction "P1.02_38") (pintype "input+no_connect"))
    )
    (net (code "89") (name "unconnected-(U4-P1.06-Pad42)") (class "Default")
      (node (ref "U4") (pin "42") (pinfunction "P1.06_42") (pintype "input+no_connect"))
    )
    (net (code "90") (name "unconnected-(U4-P1.09-Pad17)") (class "Default")
      (node (ref "U4") (pin "17") (pinfunction "P1.09_17") (pintype "input+no_connect"))
    )
    (net (code "91") (name "unconnected-(U4-P1.10-Pad2)") (class "Default")
      (node (ref "U4") (pin "2") (pinfunction "P1.10_2") (pintype "input+no_connect"))
    )
    (net (code "92") (name "unconnected-(U4-P1.11-Pad1)") (class "Default")
      (node (ref "U4") (pin "1") (pinfunction "P1.11_1") (pintype "input+no_connect"))
    )
    (net (code "93") (name "unconnected-(U4-P1.13-Pad6)") (class "Default")
      (node (ref "U4") (pin "6") (pinfunction "P1.13_6") (pintype "input+no_connect"))
    )
    (net (code "94") (name "unconnected-(U4-P12-Pad20)") (class "Default")
      (node (ref "U4") (pin "20") (pinfunction "P12_20") (pintype "input+no_connect"))
    )
    (net (code "95") (name "unconnected-(U4-P15-Pad28)") (class "Default")
      (node (ref "U4") (pin "28") (pinfunction "P15_28") (pintype "input+no_connect"))
    )
    (net (code "96") (name "unconnected-(U4-P17-Pad30)") (class "Default")
      (node (ref "U4") (pin "30") (pinfunction "P17_30") (pintype "input+no_connect"))
    )
    (net (code "97") (name "unconnected-(U4-XL1-Pad11)") (class "Default")
      (node (ref "U4") (pin "11") (pinfunction "XL1_11") (pintype "input+no_connect"))
    )
    (net (code "98") (name "unconnected-(U4-XL2-Pad13)") (class "Default")
      (node (ref "U4") (pin "13") (pinfunction "XL2_13") (pintype "input+no_connect"))
    )
    (net (code "99") (name "unconnected-(U5-AI0-Pad7)") (class "Default")
      (node (ref "U5") (pin "7") (pinfunction "AI0_7") (pintype "input+no_connect"))
    )
    (net (code "100") (name "unconnected-(U5-AI2-Pad18)") (class "Default")
      (node (ref "U5") (pin "18") (pinfunction "AI2_18") (pintype "input+no_connect"))
    )
    (net (code "101") (name "unconnected-(U5-AI3-Pad15)") (class "Default")
      (node (ref "U5") (pin "15") (pinfunction "AI3_15") (pintype "input+no_connect"))
    )
    (net (code "102") (name "unconnected-(U5-AI4-Pad4)") (class "Default")
      (node (ref "U5") (pin "4") (pinfunction "AI4_4") (pintype "input+no_connect"))
    )
    (net (code "103") (name "unconnected-(U5-AI5-Pad8)") (class "Default")
      (node (ref "U5") (pin "8") (pinfunction "AI5_8") (pintype "input+no_connect"))
    )
    (net (code "104") (name "unconnected-(U5-AI6-Pad10)") (class "Default")
      (node (ref "U5") (pin "10") (pinfunction "AI6_10") (pintype "input+no_connect"))
    )
    (net (code "105") (name "unconnected-(U5-AI7-Pad9)") (class "Default")
      (node (ref "U5") (pin "9") (pinfunction "AI7_9") (pintype "input+no_connect"))
    )
    (net (code "106") (name "unconnected-(U5-DCH-Pad25)") (class "Default")
      (node (ref "U5") (pin "25") (pinfunction "DCH_25") (pintype "input+no_connect"))
    )
    (net (code "107") (name "unconnected-(U5-NF1-Pad41)") (class "Default")
      (node (ref "U5") (pin "41") (pinfunction "NF1_41") (pintype "input+no_connect"))
    )
    (net (code "108") (name "unconnected-(U5-NF2-Pad43)") (class "Default")
      (node (ref "U5") (pin "43") (pinfunction "NF2_43") (pintype "input+no_connect"))
    )
    (net (code "109") (name "unconnected-(U5-P0.03-Pad3)") (class "Default")
      (node (ref "U5") (pin "3") (pinfunction "P0.03_3") (pintype "input+no_connect"))
    )
    (net (code "110") (name "unconnected-(U5-P0.06-Pad14)") (class "Default")
      (node (ref "U5") (pin "14") (pinfunction "P0.06_14") (pintype "input+no_connect"))
    )
    (net (code "111") (name "unconnected-(U5-P0.07-Pad22)") (class "Default")
      (node (ref "U5") (pin "22") (pinfunction "P0.07_22") (pintype "input+no_connect"))
    )
    (net (code "112") (name "unconnected-(U5-P0.08-Pad16)") (class "Default")
      (node (ref "U5") (pin "16") (pinfunction "P0.08_16") (pintype "input+no_connect"))
    )
    (net (code "113") (name "unconnected-(U5-P0.13-Pad33)") (class "Default")
      (node (ref "U5") (pin "33") (pinfunction "P0.13_33") (pintype "input+no_connect"))
    )
    (net (code "114") (name "unconnected-(U5-P0.20-Pad32)") (class "Default")
      (node (ref "U5") (pin "32") (pinfunction "P0.20_32") (pintype "input+no_connect"))
    )
    (net (code "115") (name "unconnected-(U5-P0.22-Pad34)") (class "Default")
      (node (ref "U5") (pin "34") (pinfunction "P0.22_34") (pintype "input+no_connect"))
    )
    (net (code "116") (name "unconnected-(U5-P0.26-Pad12)") (class "Default")
      (node (ref "U5") (pin "12") (pinfunction "P0.26_12") (pintype "input+no_connect"))
    )
    (net (code "117") (name "unconnected-(U5-P1.00-Pad36)") (class "Default")
      (node (ref "U5") (pin "36") (pinfunction "P1.00_36") (pintype "input+no_connect"))
    )
    (net (code "118") (name "unconnected-(U5-P1.02-Pad38)") (class "Default")
      (node (ref "U5") (pin "38") (pinfunction "P1.02_38") (pintype "input+no_connect"))
    )
    (net (code "119") (name "unconnected-(U5-P1.06-Pad42)") (class "Default")
      (node (ref "U5") (pin "42") (pinfunction "P1.06_42") (pintype "input+no_connect"))
    )
    (net (code "120") (name "unconnected-(U5-P1.09-Pad17)") (class "Default")
      (node (ref "U5") (pin "17") (pinfunction "P1.09_17") (pintype "input+no_connect"))
    )
    (net (code "121") (name "unconnected-(U5-P1.10-Pad2)") (class "Default")
      (node (ref "U5") (pin "2") (pinfunction "P1.10_2") (pintype "input+no_connect"))
    )
    (net (code "122") (name "unconnected-(U5-P1.11-Pad1)") (class "Default")
      (node (ref "U5") (pin "1") (pinfunction "P1.11_1") (pintype "input+no_connect"))
    )
    (net (code "123") (name "unconnected-(U5-P1.13-Pad6)") (class "Default")
      (node (ref "U5") (pin "6") (pinfunction "P1.13_6") (pintype "input+no_connect"))
    )
    (net (code "124") (name "unconnected-(U5-P12-Pad20)") (class "Default")
      (node (ref "U5") (pin "20") (pinfunction "P12_20") (pintype "input+no_connect"))
    )
    (net (code "125") (name "unconnected-(U5-P15-Pad28)") (class "Default")
      (node (ref "U5") (pin "28") (pinfunction "P15_28") (pintype "input+no_connect"))
    )
    (net (code "126") (name "unconnected-(U5-P17-Pad30)") (class "Default")
      (node (ref "U5") (pin "30") (pinfunction "P17_30") (pintype "input+no_connect"))
    )
    (net (code "127") (name "unconnected-(U5-XL1-Pad11)") (class "Default")
      (node (ref "U5") (pin "11") (pinfunction "XL1_11") (pintype "input+no_connect"))
    )
    (net (code "128") (name "unconnected-(U5-XL2-Pad13)") (class "Default")
      (node (ref "U5") (pin "13") (pinfunction "XL2_13") (pintype "input+no_connect"))
    )
    (net (code "129") (name "unconnected-(U6-AI0-Pad7)") (class "Default")
      (node (ref "U6") (pin "7") (pinfunction "AI0_7") (pintype "input+no_connect"))
    )
    (net (code "130") (name "unconnected-(U6-AI2-Pad18)") (class "Default")
      (node (ref "U6") (pin "18") (pinfunction "AI2_18") (pintype "input+no_connect"))
    )
    (net (code "131") (name "unconnected-(U6-AI3-Pad15)") (class "Default")
      (node (ref "U6") (pin "15") (pinfunction "AI3_15") (pintype "input+no_connect"))
    )
    (net (code "132") (name "unconnected-(U6-AI4-Pad4)") (class "Default")
      (node (ref "U6") (pin "4") (pinfunction "AI4_4") (pintype "input+no_connect"))
    )
    (net (code "133") (name "unconnected-(U6-AI5-Pad8)") (class "Default")
      (node (ref "U6") (pin "8") (pinfunction "AI5_8") (pintype "input+no_connect"))
    )
    (net (code "134") (name "unconnected-(U6-AI6-Pad10)") (class "Default")
      (node (ref "U6") (pin "10") (pinfunction "AI6_10") (pintype "input+no_connect"))
    )
    (net (code "135") (name "unconnected-(U6-AI7-Pad9)") (class "Default")
      (node (ref "U6") (pin "9") (pinfunction "AI7_9") (pintype "input+no_connect"))
    )
    (net (code "136") (name "unconnected-(U6-DCH-Pad25)") (class "Default")
      (node (ref "U6") (pin "25") (pinfunction "DCH_25") (pintype "input+no_connect"))
    )
    (net (code "137") (name "unconnected-(U6-NF1-Pad41)") (class "Default")
      (node (ref "U6") (pin "41") (pinfunction "NF1_41") (pintype "input+no_connect"))
    )
    (net (code "138") (name "unconnected-(U6-NF2-Pad43)") (class "Default")
      (node (ref "U6") (pin "43") (pinfunction "NF2_43") (pintype "input+no_connect"))
    )
    (net (code "139") (name "unconnected-(U6-P0.03-Pad3)") (class "Default")
      (node (ref "U6") (pin "3") (pinfunction "P0.03_3") (pintype "input+no_connect"))
    )
    (net (code "140") (name "unconnected-(U6-P0.06-Pad14)") (class "Default")
      (node (ref "U6") (pin "14") (pinfunction "P0.06_14") (pintype "input+no_connect"))
    )
    (net (code "141") (name "unconnected-(U6-P0.07-Pad22)") (class "Default")
      (node (ref "U6") (pin "22") (pinfunction "P0.07_22") (pintype "input+no_connect"))
    )
    (net (code "142") (name "unconnected-(U6-P0.08-Pad16)") (class "Default")
      (node (ref "U6") (pin "16") (pinfunction "P0.08_16") (pintype "input+no_connect"))
    )
    (net (code "143") (name "unconnected-(U6-P0.13-Pad33)") (class "Default")
      (node (ref "U6") (pin "33") (pinfunction "P0.13_33") (pintype "input+no_connect"))
    )
    (net (code "144") (name "unconnected-(U6-P0.20-Pad32)") (class "Default")
      (node (ref "U6") (pin "32") (pinfunction "P0.20_32") (pintype "input+no_connect"))
    )
    (net (code "145") (name "unconnected-(U6-P0.22-Pad34)") (class "Default")
      (node (ref "U6") (pin "34") (pinfunction "P0.22_34") (pintype "input+no_connect"))
    )
    (net (code "146") (name "unconnected-(U6-P0.26-Pad12)") (class "Default")
      (node (ref "U6") (pin "12") (pinfunction "P0.26_12") (pintype "input+no_connect"))
    )
    (net (code "147") (name "unconnected-(U6-P1.00-Pad36)") (class "Default")
      (node (ref "U6") (pin "36") (pinfunction "P1.00_36") (pintype "input+no_connect"))
    )
    (net (code "148") (name "unconnected-(U6-P1.02-Pad38)") (class "Default")
      (node (ref "U6") (pin "38") (pinfunction "P1.02_38") (pintype "input+no_connect"))
    )
    (net (code "149") (name "unconnected-(U6-P1.06-Pad42)") (class "Default")
      (node (ref "U6") (pin "42") (pinfunction "P1.06_42") (pintype "input+no_connect"))
    )
    (net (code "150") (name "unconnected-(U6-P1.09-Pad17)") (class "Default")
      (node (ref "U6") (pin "17") (pinfunction "P1.09_17") (pintype "input+no_connect"))
    )
    (net (code "151") (name "unconnected-(U6-P1.10-Pad2)") (class "Default")
      (node (ref "U6") (pin "2") (pinfunction "P1.10_2") (pintype "input+no_connect"))
    )
    (net (code "152") (name "unconnected-(U6-P1.11-Pad1)") (class "Default")
      (node (ref "U6") (pin "1") (pinfunction "P1.11_1") (pintype "input+no_connect"))
    )
    (net (code "153") (name "unconnected-(U6-P1.13-Pad6)") (class "Default")
      (node (ref "U6") (pin "6") (pinfunction "P1.13_6") (pintype "input+no_connect"))
    )
    (net (code "154") (name "unconnected-(U6-P12-Pad20)") (class "Default")
      (node (ref "U6") (pin "20") (pinfunction "P12_20") (pintype "input+no_connect"))
    )
    (net (code "155") (name "unconnected-(U6-P15-Pad28)") (class "Default")
      (node (ref "U6") (pin "28") (pinfunction "P15_28") (pintype "input+no_connect"))
    )
    (net (code "156") (name "unconnected-(U6-P17-Pad30)") (class "Default")
      (node (ref "U6") (pin "30") (pinfunction "P17_30") (pintype "input+no_connect"))
    )
    (net (code "157") (name "unconnected-(U6-XL1-Pad11)") (class "Default")
      (node (ref "U6") (pin "11") (pinfunction "XL1_11") (pintype "input+no_connect"))
    )
    (net (code "158") (name "unconnected-(U6-XL2-Pad13)") (class "Default")
      (node (ref "U6") (pin "13") (pinfunction "XL2_13") (pintype "input+no_connect"))
    )
  )
)
